# riffleito-CTD-REVA.net
KiCad netlist of a schematic drawn in EAGLE
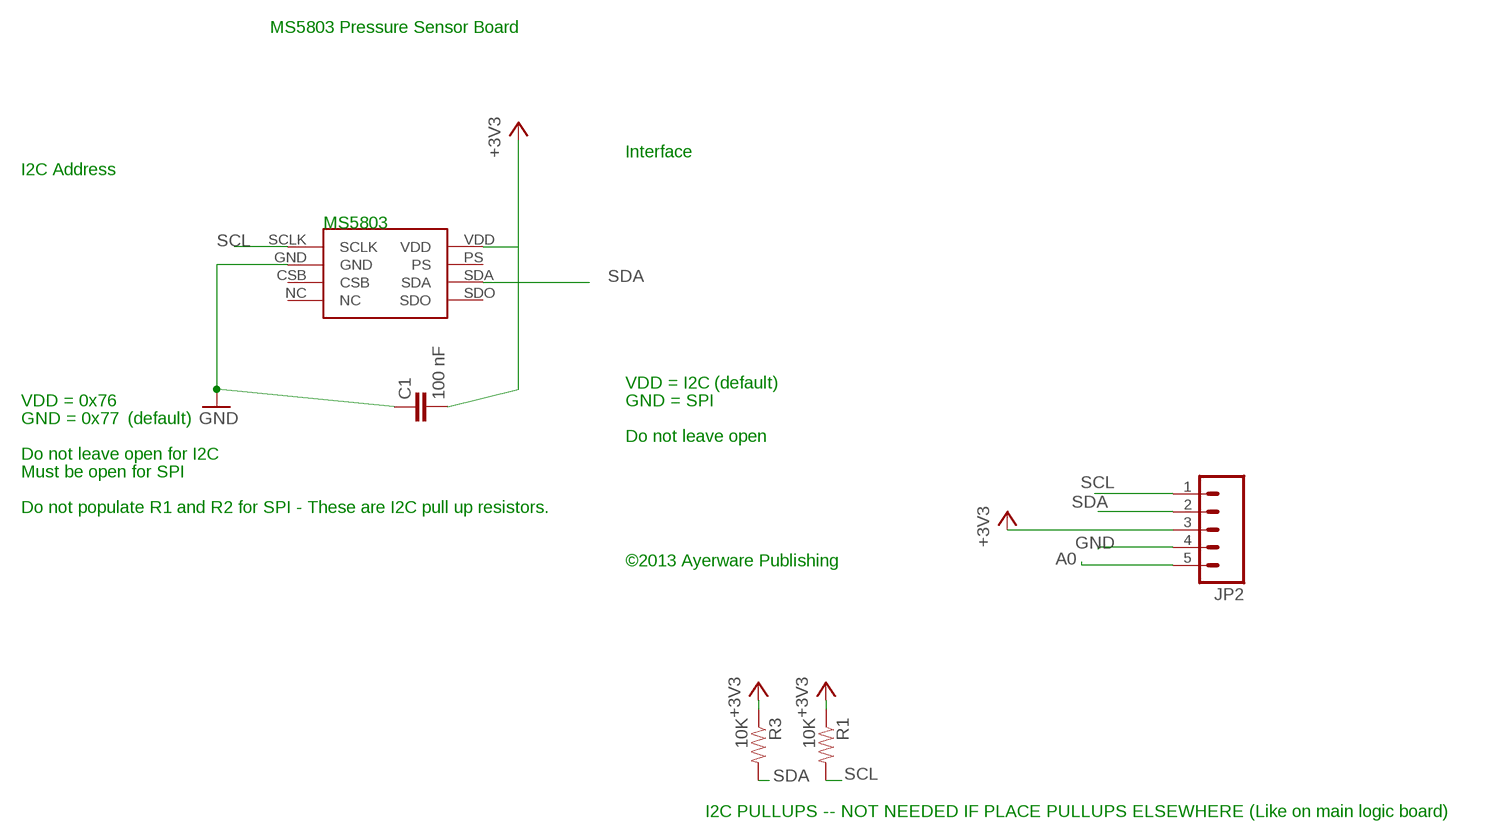
[diagram p0: schematic, sheet 1]

(export (version "E")
  (design (tool "Eeschema 10.0.6"))
  (components
    (comp (ref "C1")
      (value "100 nF")
      (footprint "eagle-import:0402-CAP")
      (libsource (lib "eagle-import") (part "CAP0402-CAP"))
    )
    (comp (ref "JP2")
      (value "M05PTH")
      (footprint "eagle-import:1X05")
      (libsource (lib "eagle-import") (part "M05PTH"))
    )
    (comp (ref "MS5803")
      (value "MS5803-14BA")
      (footprint "eagle-import:MS5803-14BA")
      (libsource (lib "eagle-import") (part "MS5803-14BA"))
    )
    (comp (ref "R1")
      (value "10K")
      (footprint "eagle-import:0402-RES")
      (libsource (lib "eagle-import") (part "RESISTOR0402-RES"))
    )
    (comp (ref "R3")
      (value "10K")
      (footprint "eagle-import:0402-RES")
      (libsource (lib "eagle-import") (part "RESISTOR0402-RES"))
    )
  )
  (nets
    (net (code "1") (name "+3V3") (class "Default")
      (node (ref "C1") (pin "1") (pinfunction "1_1") (pintype "passive"))
      (node (ref "JP2") (pin "3") (pinfunction "3_3") (pintype "passive"))
      (node (ref "MS5803") (pin "VDD") (pinfunction "VDD_VDD") (pintype "bidirectional"))
      (node (ref "R1") (pin "1") (pinfunction "1_1") (pintype "passive"))
      (node (ref "R3") (pin "1") (pinfunction "1_1") (pintype "passive"))
    )
    (net (code "2") (name "/A0") (class "Default")
      (node (ref "JP2") (pin "5") (pinfunction "5_5") (pintype "passive"))
    )
    (net (code "3") (name "/SCL") (class "Default")
      (node (ref "JP2") (pin "1") (pinfunction "1_1") (pintype "passive"))
      (node (ref "MS5803") (pin "SCLK") (pinfunction "SCLK_SCLK") (pintype "bidirectional"))
      (node (ref "R1") (pin "2") (pinfunction "2_2") (pintype "passive"))
    )
    (net (code "4") (name "/SDA") (class "Default")
      (node (ref "JP2") (pin "2") (pinfunction "2_2") (pintype "passive"))
      (node (ref "MS5803") (pin "SDA") (pinfunction "SDA_SDA") (pintype "bidirectional"))
      (node (ref "R3") (pin "2") (pinfunction "2_2") (pintype "passive"))
    )
    (net (code "5") (name "GND") (class "Default")
      (node (ref "C1") (pin "2") (pinfunction "2_2") (pintype "passive"))
      (node (ref "JP2") (pin "4") (pinfunction "4_4") (pintype "passive"))
      (node (ref "MS5803") (pin "GND") (pinfunction "GND_GND") (pintype "bidirectional"))
    )
    (net (code "6") (name "unconnected-(MS5803-PadCSB)") (class "Default")
      (node (ref "MS5803") (pin "CSB") (pinfunction "CSB_CSB") (pintype "bidirectional"))
    )
    (net (code "7") (name "unconnected-(MS5803-PadNC)") (class "Default")
      (node (ref "MS5803") (pin "NC") (pinfunction "NC_NC") (pintype "bidirectional"))
    )
    (net (code "8") (name "unconnected-(MS5803-PadPS)") (class "Default")
      (node (ref "MS5803") (pin "PS") (pinfunction "PS_PS") (pintype "bidirectional"))
    )
    (net (code "9") (name "unconnected-(MS5803-PadSDO)") (class "Default")
      (node (ref "MS5803") (pin "SDO") (pinfunction "SDO_SDO") (pintype "bidirectional"))
    )
  )
)
